# IR-Receiver-v10.net
KiCad netlist of a schematic drawn in EAGLE
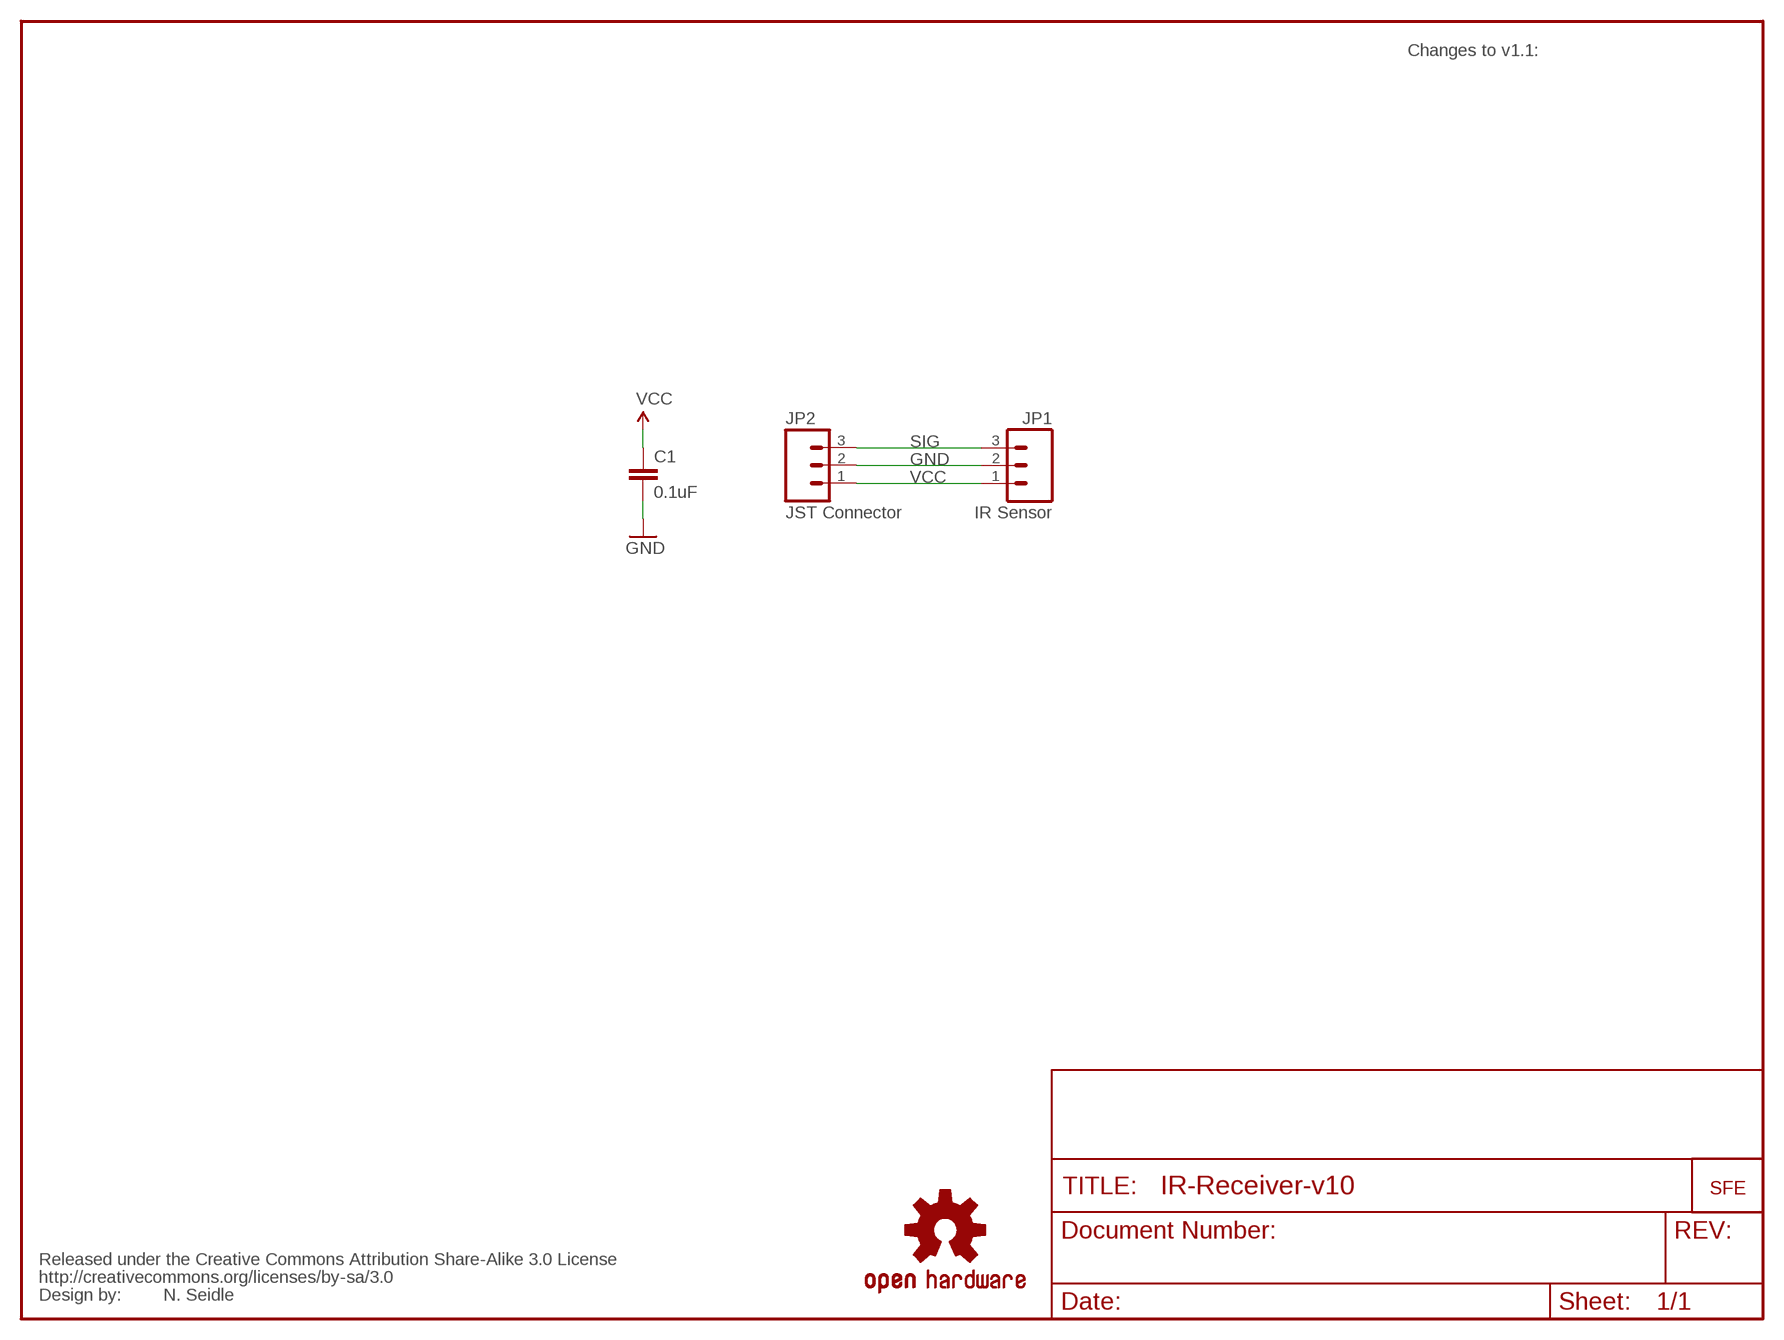
[diagram p0: schematic, sheet 1]

(export (version "E")
  (design (tool "Eeschema 10.0.6"))
  (components
    (comp (ref "C1")
      (value "0.1uF")
      (footprint "eagle-import:CAP-PTH-SMALL2")
      (libsource (lib "eagle-import") (part "CAPPTH2"))
    )
    (comp (ref "JP1")
      (value "IR Sensor")
      (footprint "eagle-import:1X03")
      (libsource (lib "eagle-import") (part "M03PTH"))
    )
    (comp (ref "JP2")
      (value "JST Connector")
      (footprint "eagle-import:JST-3-PTH")
      (libsource (lib "eagle-import") (part "M03JST-PTH"))
    )
    (comp (ref "U$1")
      (value "LOGO-SFESK")
      (footprint "eagle-import:SFE-LOGO-FLAME")
      (libsource (lib "eagle-import") (part "LOGO-SFESK"))
    )
    (comp (ref "U$2")
      (value "CREATIVE_COMMONS")
      (footprint "eagle-import:CREATIVE_COMMONS")
      (libsource (lib "eagle-import") (part "CREATIVE_COMMONS"))
    )
    (comp (ref "U$4")
      (value "OSHW-LOGOS")
      (footprint "eagle-import:OSHW-LOGO-S")
      (libsource (lib "eagle-import") (part "OSHW-LOGOS"))
    )
  )
  (nets
    (net (code "1") (name "/SIG") (class "Default")
      (node (ref "JP1") (pin "3") (pinfunction "3_3") (pintype "passive"))
      (node (ref "JP2") (pin "3") (pinfunction "3_3") (pintype "passive"))
    )
    (net (code "2") (name "GND") (class "Default")
      (node (ref "C1") (pin "2") (pinfunction "2_2") (pintype "passive"))
      (node (ref "JP1") (pin "2") (pinfunction "2_2") (pintype "passive"))
      (node (ref "JP2") (pin "2") (pinfunction "2_2") (pintype "passive"))
    )
    (net (code "3") (name "VCC") (class "Default")
      (node (ref "C1") (pin "1") (pinfunction "1_1") (pintype "passive"))
      (node (ref "JP1") (pin "1") (pinfunction "1_1") (pintype "passive"))
      (node (ref "JP2") (pin "1") (pinfunction "1_1") (pintype "passive"))
    )
  )
)
